# SAM_E54_Xplained_Pro_Target_MCU.net
KiCad netlist of a schematic drawn in Altium Designer
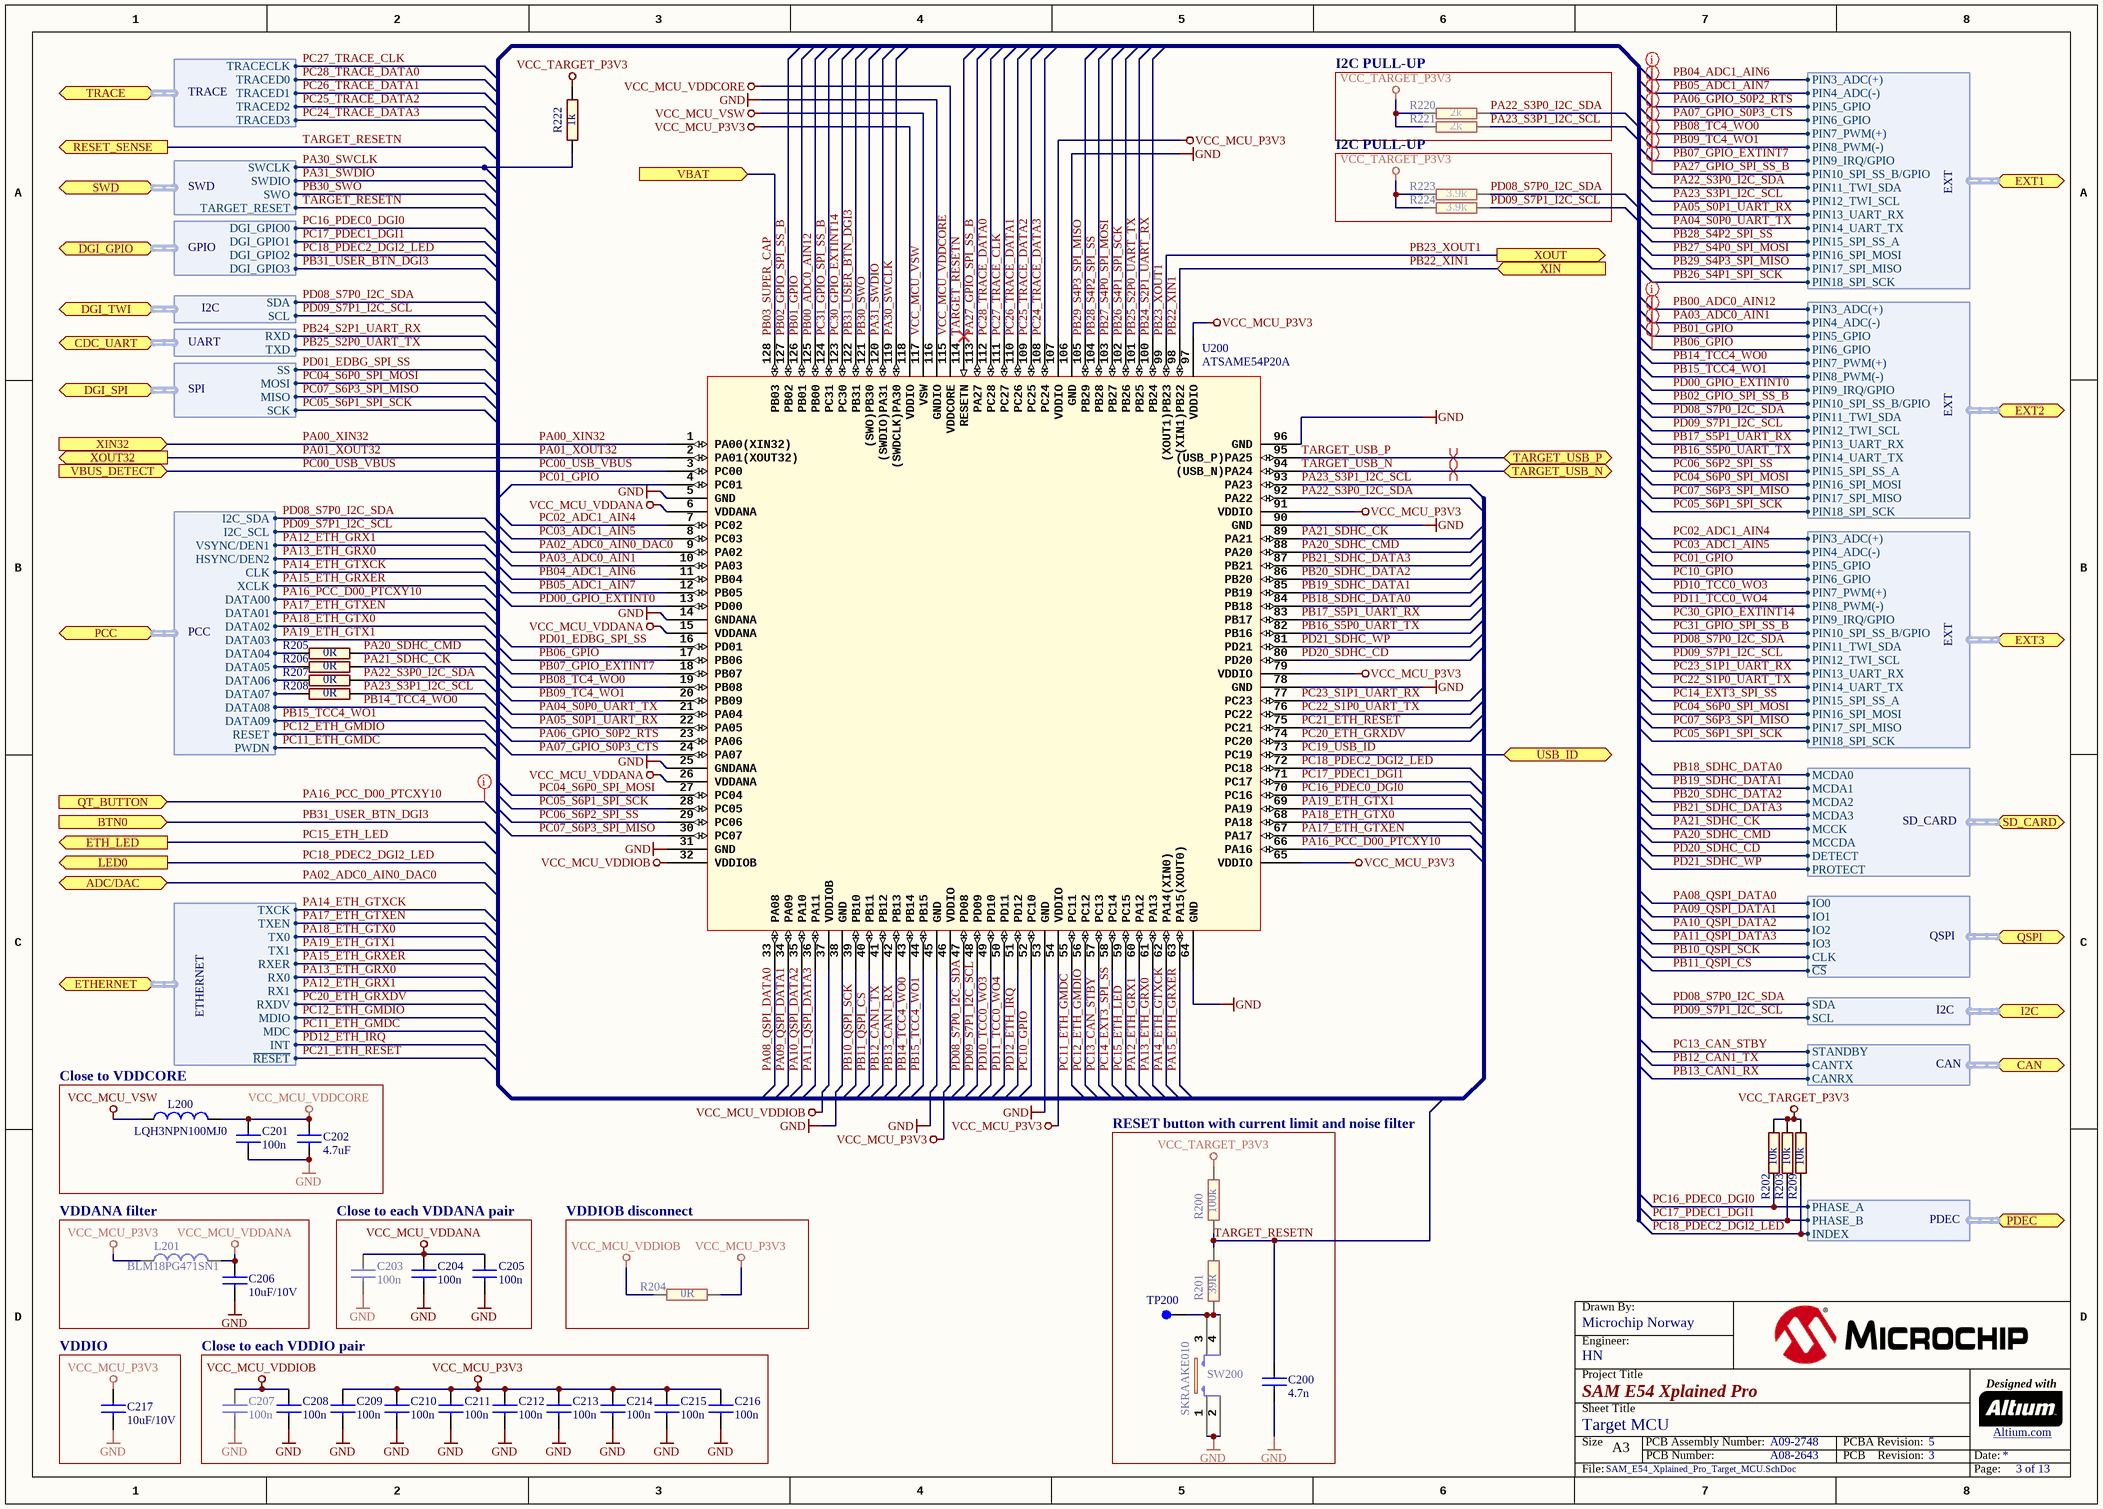
[diagram p0: SAM_E54_Xplained_Pro_Target_MCU.SchDoc]

(export (version "E")
  (design (tool "Eeschema 10.0.6"))
  (components
    (comp (ref "C200")
      (value "4.7n")
      (footprint "AP1-00053")
      (description "Ceramic capacitor, SMD 0402, X7R, 25V, +/-10% (de35287)")
      (fields (field (name "TOLERANCE") "25V, +/-10%") (field (name "MANUFACTURER") "PHYCOMP"))
      (libsource (lib "AltiumDbLib") (part "CAP-NONPOL"))
    )
    (comp (ref "C201")
      (value "100n")
      (footprint "AP1-00053")
      (description "Ceramic capacitor, SMD 0402, X7R, 16V, +/-10%")
      (fields (field (name "TOLERANCE") "16V, +/-10%") (field (name "MANUFACTURER") "Kemet"))
      (libsource (lib "AltiumDbLib") (part "CAP-NONPOL"))
    )
    (comp (ref "C202")
      (value "4.7uF")
      (footprint "AP1-00117")
      (description "Ceramic capacitor, SMD 0603, X5R, 10V, 10% (de31036)")
      (fields (field (name "TOLERANCE") "10%") (field (name "MANUFACTURER") "WALSIN Technology Corporation"))
      (libsource (lib "AltiumDbLib") (part "CAP-NONPOL"))
    )
    (comp (ref "C203")
      (value "100n")
      (footprint "AP1-00053")
      (description "Ceramic capacitor, SMD 0402, X7R, 16V, +/-10%")
      (fields (field (name "TOLERANCE") "16V, +/-10%") (field (name "MANUFACTURER") "Kemet"))
      (libsource (lib "AltiumDbLib") (part "CAP-NONPOL"))
    )
    (comp (ref "C204")
      (value "100n")
      (footprint "AP1-00053")
      (description "Ceramic capacitor, SMD 0402, X7R, 16V, +/-10%")
      (fields (field (name "TOLERANCE") "16V, +/-10%") (field (name "MANUFACTURER") "Kemet"))
      (libsource (lib "AltiumDbLib") (part "CAP-NONPOL"))
    )
    (comp (ref "C205")
      (value "100n")
      (footprint "AP1-00053")
      (description "Ceramic capacitor, SMD 0402, X7R, 16V, +/-10%")
      (fields (field (name "TOLERANCE") "16V, +/-10%") (field (name "MANUFACTURER") "Kemet"))
      (libsource (lib "AltiumDbLib") (part "CAP-NONPOL"))
    )
    (comp (ref "C206")
      (value "10uF/10V")
      (footprint "AP1-00117")
      (description "Ceramic capacitor, SMD 0603, X5R, 10V, 10UF Â± 20%")
      (fields (field (name "MANUFACTURER") "AVX") (field (name "MPN") "0603ZD106MAT2A"))
      (libsource (lib "AltiumDbLib") (part "CAP-NONPOL"))
    )
    (comp (ref "C207")
      (value "100n")
      (footprint "AP1-00053")
      (description "Ceramic capacitor, SMD 0402, X7R, 16V, +/-10%")
      (fields (field (name "TOLERANCE") "16V, +/-10%") (field (name "MANUFACTURER") "Kemet"))
      (libsource (lib "AltiumDbLib") (part "CAP-NONPOL"))
    )
    (comp (ref "C208")
      (value "100n")
      (footprint "AP1-00053")
      (description "Ceramic capacitor, SMD 0402, X7R, 16V, +/-10%")
      (fields (field (name "TOLERANCE") "16V, +/-10%") (field (name "MANUFACTURER") "Kemet"))
      (libsource (lib "AltiumDbLib") (part "CAP-NONPOL"))
    )
    (comp (ref "C209")
      (value "100n")
      (footprint "AP1-00053")
      (description "Ceramic capacitor, SMD 0402, X7R, 16V, +/-10%")
      (fields (field (name "TOLERANCE") "16V, +/-10%") (field (name "MANUFACTURER") "Kemet"))
      (libsource (lib "AltiumDbLib") (part "CAP-NONPOL"))
    )
    (comp (ref "C210")
      (value "100n")
      (footprint "AP1-00053")
      (description "Ceramic capacitor, SMD 0402, X7R, 16V, +/-10%")
      (fields (field (name "TOLERANCE") "16V, +/-10%") (field (name "MANUFACTURER") "Kemet"))
      (libsource (lib "AltiumDbLib") (part "CAP-NONPOL"))
    )
    (comp (ref "C211")
      (value "100n")
      (footprint "AP1-00053")
      (description "Ceramic capacitor, SMD 0402, X7R, 16V, +/-10%")
      (fields (field (name "TOLERANCE") "16V, +/-10%") (field (name "MANUFACTURER") "Kemet"))
      (libsource (lib "AltiumDbLib") (part "CAP-NONPOL"))
    )
    (comp (ref "C212")
      (value "100n")
      (footprint "AP1-00053")
      (description "Ceramic capacitor, SMD 0402, X7R, 16V, +/-10%")
      (fields (field (name "TOLERANCE") "16V, +/-10%") (field (name "MANUFACTURER") "Kemet"))
      (libsource (lib "AltiumDbLib") (part "CAP-NONPOL"))
    )
    (comp (ref "C213")
      (value "100n")
      (footprint "AP1-00053")
      (description "Ceramic capacitor, SMD 0402, X7R, 16V, +/-10%")
      (fields (field (name "TOLERANCE") "16V, +/-10%") (field (name "MANUFACTURER") "Kemet"))
      (libsource (lib "AltiumDbLib") (part "CAP-NONPOL"))
    )
    (comp (ref "C214")
      (value "100n")
      (footprint "AP1-00053")
      (description "Ceramic capacitor, SMD 0402, X7R, 16V, +/-10%")
      (fields (field (name "TOLERANCE") "16V, +/-10%") (field (name "MANUFACTURER") "Kemet"))
      (libsource (lib "AltiumDbLib") (part "CAP-NONPOL"))
    )
    (comp (ref "C215")
      (value "100n")
      (footprint "AP1-00053")
      (description "Ceramic capacitor, SMD 0402, X7R, 16V, +/-10%")
      (fields (field (name "TOLERANCE") "16V, +/-10%") (field (name "MANUFACTURER") "Kemet"))
      (libsource (lib "AltiumDbLib") (part "CAP-NONPOL"))
    )
    (comp (ref "C216")
      (value "100n")
      (footprint "AP1-00053")
      (description "Ceramic capacitor, SMD 0402, X7R, 16V, +/-10%")
      (fields (field (name "TOLERANCE") "16V, +/-10%") (field (name "MANUFACTURER") "Kemet"))
      (libsource (lib "AltiumDbLib") (part "CAP-NONPOL"))
    )
    (comp (ref "C217")
      (value "10uF/10V")
      (footprint "AP1-00117")
      (description "Ceramic capacitor, SMD 0603, X5R, 10V, 10UF Â± 20%")
      (fields (field (name "MANUFACTURER") "AVX") (field (name "MPN") "0603ZD106MAT2A"))
      (libsource (lib "AltiumDbLib") (part "CAP-NONPOL"))
    )
    (comp (ref "L200")
      (value "LQH3NPN100MJ0")
      (footprint "AP3-00115")
      (description "10uH power inductor, Isat = 560mA , Itemp = 710mA, Rdc = 0.360ohm")
      (fields (field (name "TOLERANCE") "Â±20%") (field (name "MANUFACTURER") "Murata"))
      (libsource (lib "AltiumDbLib") (part "INDUCTOR"))
    )
    (comp (ref "L201")
      (value "BLM18PG471SN1")
      (footprint "AP3-00005")
      (description "SMD RF inductor 0603. Z=470Ohm (@100MHz), Max R(dc)=0.65Ohm, Max current=1A")
      (fields (field (name "MANUFACTURER") "Murata"))
      (libsource (lib "AltiumDbLib") (part "INDUCTOR"))
    )
    (comp (ref "R200")
      (value "100k")
      (footprint "AP2-00011")
      (description "Thick film resistor, SMD 0402, 1/16W, 1%")
      (fields (field (name "TOLERANCE") "1 %") (field (name "MANUFACTURER") "ASJ"))
      (libsource (lib "AltiumDbLib") (part "R2"))
    )
    (comp (ref "R201")
      (value "39R")
      (footprint "AP2-00011")
      (description "Thick film resistor, SMD 0402, 1/16W, 1%")
      (fields (field (name "TOLERANCE") "1 %") (field (name "MANUFACTURER") "ASJ"))
      (libsource (lib "") (part "R2_3"))
    )
    (comp (ref "R202")
      (value "10k")
      (footprint "AP2-00011")
      (description "Thick film resistor, SMD 0402, 1/16W, 1%")
      (fields (field (name "TOLERANCE") "1 %") (field (name "MANUFACTURER") "vishay"))
      (libsource (lib "AltiumDbLib") (part "R2"))
    )
    (comp (ref "R203")
      (value "10k")
      (footprint "AP2-00011")
      (description "Thick film resistor, SMD 0402, 1/16W, 1%")
      (fields (field (name "TOLERANCE") "1 %") (field (name "MANUFACTURER") "vishay"))
      (libsource (lib "") (part "R2_2"))
    )
    (comp (ref "R204")
      (value "0R")
      (footprint "AP2-00000")
      (description "RES 0.0 OHM 1/16W 0402 SMD")
      (fields (field (name "TOLERANCE") "1 %") (field (name "MANUFACTURER") "(n/a)"))
      (libsource (lib "") (part "R2_1"))
    )
    (comp (ref "R205")
      (value "0R")
      (footprint "AP2-00000")
      (description "RES 0.0 OHM 1/16W 0402 SMD")
      (fields (field (name "TOLERANCE") "1 %") (field (name "MANUFACTURER") "(n/a)"))
      (libsource (lib "") (part "R2_1"))
    )
    (comp (ref "R206")
      (value "0R")
      (footprint "AP2-00000")
      (description "RES 0.0 OHM 1/16W 0402 SMD")
      (fields (field (name "TOLERANCE") "1 %") (field (name "MANUFACTURER") "(n/a)"))
      (libsource (lib "") (part "R2_1"))
    )
    (comp (ref "R207")
      (value "0R")
      (footprint "AP2-00000")
      (description "RES 0.0 OHM 1/16W 0402 SMD")
      (fields (field (name "TOLERANCE") "1 %") (field (name "MANUFACTURER") "(n/a)"))
      (libsource (lib "") (part "R2_1"))
    )
    (comp (ref "R208")
      (value "0R")
      (footprint "AP2-00000")
      (description "RES 0.0 OHM 1/16W 0402 SMD")
      (fields (field (name "TOLERANCE") "1 %") (field (name "MANUFACTURER") "(n/a)"))
      (libsource (lib "") (part "R2_1"))
    )
    (comp (ref "R209")
      (value "10k")
      (footprint "AP2-00011")
      (description "Thick film resistor, SMD 0402, 1/16W, 1%")
      (fields (field (name "TOLERANCE") "1 %") (field (name "MANUFACTURER") "vishay"))
      (libsource (lib "") (part "R2_2"))
    )
    (comp (ref "R220")
      (value "2k")
      (footprint "AP2-00011")
      (description "Thick film resistor, SMD 0402, 1/16W, 1%")
      (fields (field (name "TOLERANCE") "1 %"))
      (libsource (lib "") (part "R2_1"))
    )
    (comp (ref "R221")
      (value "2k")
      (footprint "AP2-00011")
      (description "Thick film resistor, SMD 0402, 1/16W, 1%")
      (fields (field (name "TOLERANCE") "1 %"))
      (libsource (lib "") (part "R2_1"))
    )
    (comp (ref "R222")
      (value "1k")
      (footprint "AP2-00011")
      (description "Thick film resistor, SMD 0402, 1/16W, 1%")
      (fields (field (name "TOLERANCE") "1 %") (field (name "MANUFACTURER") "ASJ"))
      (libsource (lib "AltiumDbLib") (part "R2"))
    )
    (comp (ref "R223")
      (value "3.9k")
      (footprint "AP2-00011")
      (description "Thick film resistor, SMD 0402, 1/16W, 1%")
      (fields (field (name "TOLERANCE") "1 %"))
      (libsource (lib "") (part "R2_1"))
    )
    (comp (ref "R224")
      (value "3.9k")
      (footprint "AP2-00011")
      (description "Thick film resistor, SMD 0402, 1/16W, 1%")
      (fields (field (name "TOLERANCE") "1 %"))
      (libsource (lib "") (part "R2_1"))
    )
    (comp (ref "SW200")
      (value "SKRAAKE010")
      (footprint "AP8-00137")
      (description "6.2x6.2 mm SMD tact switch, same as A08-0091 but less force is needed")
      (fields (field (name "MANUFACTURER") "ALPS"))
      (libsource (lib "AltiumDbLib") (part "PUSHBUTTON1"))
    )
    (comp (ref "TP200")
      (value "~")
      (footprint "AP8-00010")
      (description "Single SMD testpad")
      (libsource (lib "AltiumDbLib") (part "TESTPOINT"))
    )
    (comp (ref "U200")
      (value "ATSAME54P20A")
      (footprint "AP6-00477")
      (description "Atmel 32-bit RISC MCU")
      (fields (field (name "MANUFACTURER") "ATMEL") (field (name "MPN") "ATSAME54P20A-AUT"))
      (libsource (lib "AltiumDbLib") (part "SAME54_TQFP128"))
    )
  )
  (nets
    (net (code "15") (name "/DATA04") (class "Default")
      (node (ref "R205") (pin "2") (pinfunction "2_2") (pintype "passive"))
    )
    (net (code "16") (name "/DATA05") (class "Default")
      (node (ref "R206") (pin "2") (pinfunction "2_2") (pintype "passive"))
    )
    (net (code "17") (name "/DATA06") (class "Default")
      (node (ref "R207") (pin "2") (pinfunction "2_2") (pintype "passive"))
    )
    (net (code "18") (name "/DATA07") (class "Default")
      (node (ref "R208") (pin "2") (pinfunction "2_2") (pintype "passive"))
    )
    (net (code "19") (name "/PA00_XIN32") (class "Default")
      (node (ref "U200") (pin "1") (pinfunction "PA00(XIN32)_1") (pintype "bidirectional"))
    )
    (net (code "20") (name "/PA01_XOUT32") (class "Default")
      (node (ref "U200") (pin "2") (pinfunction "PA01(XOUT32)_2") (pintype "bidirectional"))
    )
    (net (code "21") (name "/PA02_ADC0_AIN0_DAC0") (class "Default")
      (node (ref "U200") (pin "9") (pinfunction "PA02_9") (pintype "bidirectional"))
    )
    (net (code "22") (name "/PA03_ADC0_AIN1") (class "Default")
      (node (ref "U200") (pin "10") (pinfunction "PA03_10") (pintype "bidirectional"))
    )
    (net (code "23") (name "/PA04_S0P0_UART_TX") (class "Default")
      (node (ref "U200") (pin "21") (pinfunction "PA04_21") (pintype "bidirectional"))
    )
    (net (code "24") (name "/PA05_S0P1_UART_RX") (class "Default")
      (node (ref "U200") (pin "22") (pinfunction "PA05_22") (pintype "bidirectional"))
    )
    (net (code "25") (name "/PA06_GPIO_S0P2_RTS") (class "Default")
      (node (ref "U200") (pin "23") (pinfunction "PA06_23") (pintype "bidirectional"))
    )
    (net (code "26") (name "/PA07_GPIO_S0P3_CTS") (class "Default")
      (node (ref "U200") (pin "24") (pinfunction "PA07_24") (pintype "bidirectional"))
    )
    (net (code "27") (name "/PA08_QSPI_DATA0") (class "Default")
      (node (ref "U200") (pin "33") (pinfunction "PA08_33") (pintype "bidirectional"))
    )
    (net (code "28") (name "/PA09_QSPI_DATA1") (class "Default")
      (node (ref "U200") (pin "34") (pinfunction "PA09_34") (pintype "bidirectional"))
    )
    (net (code "29") (name "/PA10_QSPI_DATA2") (class "Default")
      (node (ref "U200") (pin "35") (pinfunction "PA10_35") (pintype "bidirectional"))
    )
    (net (code "30") (name "/PA11_QSPI_DATA3") (class "Default")
      (node (ref "U200") (pin "36") (pinfunction "PA11_36") (pintype "bidirectional"))
    )
    (net (code "31") (name "/PA12_ETH_GRX1") (class "Default")
      (node (ref "U200") (pin "60") (pinfunction "PA12_60") (pintype "bidirectional"))
    )
    (net (code "32") (name "/PA13_ETH_GRX0") (class "Default")
      (node (ref "U200") (pin "61") (pinfunction "PA13_61") (pintype "bidirectional"))
    )
    (net (code "33") (name "/PA14_ETH_GTXCK") (class "Default")
      (node (ref "U200") (pin "62") (pinfunction "PA14(XIN0)_62") (pintype "bidirectional"))
    )
    (net (code "34") (name "/PA15_ETH_GRXER") (class "Default")
      (node (ref "U200") (pin "63") (pinfunction "PA15(XOUT0)_63") (pintype "bidirectional"))
    )
    (net (code "35") (name "/PA16_PCC_D00_PTCXY10") (class "Default")
      (node (ref "U200") (pin "66") (pinfunction "PA16_66") (pintype "bidirectional"))
    )
    (net (code "36") (name "/PA17_ETH_GTXEN") (class "Default")
      (node (ref "U200") (pin "67") (pinfunction "PA17_67") (pintype "bidirectional"))
    )
    (net (code "37") (name "/PA18_ETH_GTX0") (class "Default")
      (node (ref "U200") (pin "68") (pinfunction "PA18_68") (pintype "bidirectional"))
    )
    (net (code "38") (name "/PA19_ETH_GTX1") (class "Default")
      (node (ref "U200") (pin "69") (pinfunction "PA19_69") (pintype "bidirectional"))
    )
    (net (code "39") (name "/PA20_SDHC_CMD") (class "Default")
      (node (ref "R205") (pin "1") (pinfunction "1_1") (pintype "passive"))
      (node (ref "U200") (pin "88") (pinfunction "PA20_88") (pintype "bidirectional"))
    )
    (net (code "40") (name "/PA21_SDHC_CK") (class "Default")
      (node (ref "R206") (pin "1") (pinfunction "1_1") (pintype "passive"))
      (node (ref "U200") (pin "89") (pinfunction "PA21_89") (pintype "bidirectional"))
    )
    (net (code "41") (name "/PA22_S3P0_I2C_SDA") (class "Default")
      (node (ref "R207") (pin "1") (pinfunction "1_1") (pintype "passive"))
      (node (ref "R220") (pin "1") (pinfunction "1_1") (pintype "passive"))
      (node (ref "U200") (pin "92") (pinfunction "PA22_92") (pintype "bidirectional"))
    )
    (net (code "42") (name "/PA23_S3P1_I2C_SCL") (class "Default")
      (node (ref "R208") (pin "1") (pinfunction "1_1") (pintype "passive"))
      (node (ref "R221") (pin "1") (pinfunction "1_1") (pintype "passive"))
      (node (ref "U200") (pin "93") (pinfunction "PA23_93") (pintype "bidirectional"))
    )
    (net (code "43") (name "/PA27_GPIO_SPI_SS_B") (class "Default")
      (node (ref "U200") (pin "113") (pinfunction "PA27_113") (pintype "bidirectional"))
    )
    (net (code "44") (name "/PA30_SWCLK") (class "Default")
      (node (ref "R222") (pin "1") (pinfunction "1_1") (pintype "passive"))
      (node (ref "U200") (pin "119") (pinfunction "(SWDCLK)PA30_119") (pintype "bidirectional"))
    )
    (net (code "45") (name "/PA31_SWDIO") (class "Default")
      (node (ref "U200") (pin "120") (pinfunction "(SWDIO)PA31_120") (pintype "bidirectional"))
    )
    (net (code "46") (name "/PB00_ADC0_AIN12") (class "Default")
      (node (ref "U200") (pin "125") (pinfunction "PB00_125") (pintype "bidirectional"))
    )
    (net (code "47") (name "/PB01_GPIO") (class "Default")
      (node (ref "U200") (pin "126") (pinfunction "PB01_126") (pintype "bidirectional"))
    )
    (net (code "48") (name "/PB02_GPIO_SPI_SS_B") (class "Default")
      (node (ref "U200") (pin "127") (pinfunction "PB02_127") (pintype "bidirectional"))
    )
    (net (code "49") (name "/PB03_SUPER_CAP") (class "Default")
      (node (ref "U200") (pin "128") (pinfunction "PB03_128") (pintype "bidirectional"))
    )
    (net (code "50") (name "/PB04_ADC1_AIN6") (class "Default")
      (node (ref "U200") (pin "11") (pinfunction "PB04_11") (pintype "bidirectional"))
    )
    (net (code "51") (name "/PB05_ADC1_AIN7") (class "Default")
      (node (ref "U200") (pin "12") (pinfunction "PB05_12") (pintype "bidirectional"))
    )
    (net (code "52") (name "/PB06_GPIO") (class "Default")
      (node (ref "U200") (pin "17") (pinfunction "PB06_17") (pintype "bidirectional"))
    )
    (net (code "53") (name "/PB07_GPIO_EXTINT7") (class "Default")
      (node (ref "U200") (pin "18") (pinfunction "PB07_18") (pintype "bidirectional"))
    )
    (net (code "54") (name "/PB08_TC4_WO0") (class "Default")
      (node (ref "U200") (pin "19") (pinfunction "PB08_19") (pintype "bidirectional"))
    )
    (net (code "55") (name "/PB09_TC4_WO1") (class "Default")
      (node (ref "U200") (pin "20") (pinfunction "PB09_20") (pintype "bidirectional"))
    )
    (net (code "56") (name "/PB10_QSPI_SCK") (class "Default")
      (node (ref "U200") (pin "39") (pinfunction "PB10_39") (pintype "bidirectional"))
    )
    (net (code "57") (name "/PB11_QSPI_CS") (class "Default")
      (node (ref "U200") (pin "40") (pinfunction "PB11_40") (pintype "bidirectional"))
    )
    (net (code "58") (name "/PB12_CAN1_TX") (class "Default")
      (node (ref "U200") (pin "41") (pinfunction "PB12_41") (pintype "bidirectional"))
    )
    (net (code "59") (name "/PB13_CAN1_RX") (class "Default")
      (node (ref "U200") (pin "42") (pinfunction "PB13_42") (pintype "bidirectional"))
    )
    (net (code "60") (name "/PB14_TCC4_WO0") (class "Default")
      (node (ref "U200") (pin "43") (pinfunction "PB14_43") (pintype "bidirectional"))
    )
    (net (code "61") (name "/PB15_TCC4_WO1") (class "Default")
      (node (ref "U200") (pin "44") (pinfunction "PB15_44") (pintype "bidirectional"))
    )
    (net (code "62") (name "/PB16_S5P0_UART_TX") (class "Default")
      (node (ref "U200") (pin "82") (pinfunction "PB16_82") (pintype "bidirectional"))
    )
    (net (code "63") (name "/PB17_S5P1_UART_RX") (class "Default")
      (node (ref "U200") (pin "83") (pinfunction "PB17_83") (pintype "bidirectional"))
    )
    (net (code "64") (name "/PB18_SDHC_DATA0") (class "Default")
      (node (ref "U200") (pin "84") (pinfunction "PB18_84") (pintype "bidirectional"))
    )
    (net (code "65") (name "/PB19_SDHC_DATA1") (class "Default")
      (node (ref "U200") (pin "85") (pinfunction "PB19_85") (pintype "bidirectional"))
    )
    (net (code "66") (name "/PB20_SDHC_DATA2") (class "Default")
      (node (ref "U200") (pin "86") (pinfunction "PB20_86") (pintype "bidirectional"))
    )
    (net (code "67") (name "/PB21_SDHC_DATA3") (class "Default")
      (node (ref "U200") (pin "87") (pinfunction "PB21_87") (pintype "bidirectional"))
    )
    (net (code "68") (name "/PB22_XIN1") (class "Default")
      (node (ref "U200") (pin "98") (pinfunction "(XIN1)PB22_98") (pintype "bidirectional"))
    )
    (net (code "69") (name "/PB23_XOUT1") (class "Default")
      (node (ref "U200") (pin "99") (pinfunction "(XOUT1)PB23_99") (pintype "bidirectional"))
    )
    (net (code "70") (name "/PB24_S2P1_UART_RX") (class "Default")
      (node (ref "U200") (pin "100") (pinfunction "PB24_100") (pintype "bidirectional"))
    )
    (net (code "71") (name "/PB25_S2P0_UART_TX") (class "Default")
      (node (ref "U200") (pin "101") (pinfunction "PB25_101") (pintype "bidirectional"))
    )
    (net (code "72") (name "/PB26_S4P1_SPI_SCK") (class "Default")
      (node (ref "U200") (pin "102") (pinfunction "PB26_102") (pintype "bidirectional"))
    )
    (net (code "73") (name "/PB27_S4P0_SPI_MOSI") (class "Default")
      (node (ref "U200") (pin "103") (pinfunction "PB27_103") (pintype "bidirectional"))
    )
    (net (code "74") (name "/PB28_S4P2_SPI_SS") (class "Default")
      (node (ref "U200") (pin "104") (pinfunction "PB28_104") (pintype "bidirectional"))
    )
    (net (code "75") (name "/PB29_S4P3_SPI_MISO") (class "Default")
      (node (ref "U200") (pin "105") (pinfunction "PB29_105") (pintype "bidirectional"))
    )
    (net (code "76") (name "/PB30_SWO") (class "Default")
      (node (ref "U200") (pin "121") (pinfunction "(SWO)PB30_121") (pintype "bidirectional"))
    )
    (net (code "77") (name "/PB31_USER_BTN_DGI3") (class "Default")
      (node (ref "U200") (pin "122") (pinfunction "PB31_122") (pintype "bidirectional"))
    )
    (net (code "78") (name "/PC00_USB_VBUS") (class "Default")
      (node (ref "U200") (pin "3") (pinfunction "PC00_3") (pintype "bidirectional"))
    )
    (net (code "79") (name "/PC01_GPIO") (class "Default")
      (node (ref "U200") (pin "4") (pinfunction "PC01_4") (pintype "bidirectional"))
    )
    (net (code "80") (name "/PC02_ADC1_AIN4") (class "Default")
      (node (ref "U200") (pin "7") (pinfunction "PC02_7") (pintype "bidirectional"))
    )
    (net (code "81") (name "/PC03_ADC1_AIN5") (class "Default")
      (node (ref "U200") (pin "8") (pinfunction "PC03_8") (pintype "bidirectional"))
    )
    (net (code "82") (name "/PC04_S6P0_SPI_MOSI") (class "Default")
      (node (ref "U200") (pin "27") (pinfunction "PC04_27") (pintype "bidirectional"))
    )
    (net (code "83") (name "/PC05_S6P1_SPI_SCK") (class "Default")
      (node (ref "U200") (pin "28") (pinfunction "PC05_28") (pintype "bidirectional"))
    )
    (net (code "84") (name "/PC06_S6P2_SPI_SS") (class "Default")
      (node (ref "U200") (pin "29") (pinfunction "PC06_29") (pintype "bidirectional"))
    )
    (net (code "85") (name "/PC07_S6P3_SPI_MISO") (class "Default")
      (node (ref "U200") (pin "30") (pinfunction "PC07_30") (pintype "bidirectional"))
    )
    (net (code "86") (name "/PC10_GPIO") (class "Default")
      (node (ref "U200") (pin "52") (pinfunction "PC10_52") (pintype "bidirectional"))
    )
    (net (code "87") (name "/PC11_ETH_GMDC") (class "Default")
      (node (ref "U200") (pin "55") (pinfunction "PC11_55") (pintype "bidirectional"))
    )
    (net (code "88") (name "/PC12_ETH_GMDIO") (class "Default")
      (node (ref "U200") (pin "56") (pinfunction "PC12_56") (pintype "bidirectional"))
    )
    (net (code "89") (name "/PC13_CAN_STBY") (class "Default")
      (node (ref "U200") (pin "57") (pinfunction "PC13_57") (pintype "bidirectional"))
    )
    (net (code "90") (name "/PC14_EXT3_SPI_SS") (class "Default")
      (node (ref "U200") (pin "58") (pinfunction "PC14_58") (pintype "bidirectional"))
    )
    (net (code "91") (name "/PC15_ETH_LED") (class "Default")
      (node (ref "U200") (pin "59") (pinfunction "PC15_59") (pintype "bidirectional"))
    )
    (net (code "92") (name "/PC16_PDEC0_DGI0") (class "Default")
      (node (ref "R202") (pin "1") (pinfunction "1_1") (pintype "passive"))
      (node (ref "U200") (pin "70") (pinfunction "PC16_70") (pintype "bidirectional"))
    )
    (net (code "93") (name "/PC17_PDEC1_DGI1") (class "Default")
      (node (ref "R203") (pin "2") (pinfunction "2_2") (pintype "passive"))
      (node (ref "U200") (pin "71") (pinfunction "PC17_71") (pintype "bidirectional"))
    )
    (net (code "94") (name "/PC18_PDEC2_DGI2_LED") (class "Default")
      (node (ref "R209") (pin "2") (pinfunction "2_2") (pintype "passive"))
      (node (ref "U200") (pin "72") (pinfunction "PC18_72") (pintype "bidirectional"))
    )
    (net (code "95") (name "/PC19_USB_ID") (class "Default")
      (node (ref "U200") (pin "73") (pinfunction "PC19_73") (pintype "bidirectional"))
    )
    (net (code "96") (name "/PC20_ETH_GRXDV") (class "Default")
      (node (ref "U200") (pin "74") (pinfunction "PC20_74") (pintype "bidirectional"))
    )
    (net (code "97") (name "/PC21_ETH_RESET") (class "Default")
      (node (ref "U200") (pin "75") (pinfunction "PC21_75") (pintype "bidirectional"))
    )
    (net (code "98") (name "/PC22_S1P0_UART_TX") (class "Default")
      (node (ref "U200") (pin "76") (pinfunction "PC22_76") (pintype "bidirectional"))
    )
    (net (code "99") (name "/PC23_S1P1_UART_RX") (class "Default")
      (node (ref "U200") (pin "77") (pinfunction "PC23_77") (pintype "bidirectional"))
    )
    (net (code "100") (name "/PC24_TRACE_DATA3") (class "Default")
      (node (ref "U200") (pin "108") (pinfunction "PC24_108") (pintype "bidirectional"))
    )
    (net (code "101") (name "/PC25_TRACE_DATA2") (class "Default")
      (node (ref "U200") (pin "109") (pinfunction "PC25_109") (pintype "bidirectional"))
    )
    (net (code "102") (name "/PC26_TRACE_DATA1") (class "Default")
      (node (ref "U200") (pin "110") (pinfunction "PC26_110") (pintype "bidirectional"))
    )
    (net (code "103") (name "/PC27_TRACE_CLK") (class "Default")
      (node (ref "U200") (pin "111") (pinfunction "PC27_111") (pintype "bidirectional"))
    )
    (net (code "104") (name "/PC28_TRACE_DATA0") (class "Default")
      (node (ref "U200") (pin "112") (pinfunction "PC28_112") (pintype "bidirectional"))
    )
    (net (code "105") (name "/PC30_GPIO_EXTINT14") (class "Default")
      (node (ref "U200") (pin "123") (pinfunction "PC30_123") (pintype "bidirectional"))
    )
    (net (code "106") (name "/PC31_GPIO_SPI_SS_B") (class "Default")
      (node (ref "U200") (pin "124") (pinfunction "PC31_124") (pintype "bidirectional"))
    )
    (net (code "107") (name "/PD00_GPIO_EXTINT0") (class "Default")
      (node (ref "U200") (pin "13") (pinfunction "PD00_13") (pintype "bidirectional"))
    )
    (net (code "108") (name "/PD01_EDBG_SPI_SS") (class "Default")
      (node (ref "U200") (pin "16") (pinfunction "PD01_16") (pintype "bidirectional"))
    )
    (net (code "109") (name "/PD08_S7P0_I2C_SDA") (class "Default")
      (node (ref "R223") (pin "1") (pinfunction "1_1") (pintype "passive"))
      (node (ref "U200") (pin "47") (pinfunction "PD08_47") (pintype "bidirectional"))
    )
    (net (code "110") (name "/PD09_S7P1_I2C_SCL") (class "Default")
      (node (ref "R224") (pin "1") (pinfunction "1_1") (pintype "passive"))
      (node (ref "U200") (pin "48") (pinfunction "PD09_48") (pintype "bidirectional"))
    )
    (net (code "111") (name "/PD10_TCC0_WO3") (class "Default")
      (node (ref "U200") (pin "49") (pinfunction "PD10_49") (pintype "bidirectional"))
    )
    (net (code "112") (name "/PD11_TCC0_WO4") (class "Default")
      (node (ref "U200") (pin "50") (pinfunction "PD11_50") (pintype "bidirectional"))
    )
    (net (code "113") (name "/PD12_ETH_IRQ") (class "Default")
      (node (ref "U200") (pin "51") (pinfunction "PD12_51") (pintype "bidirectional"))
    )
    (net (code "114") (name "/PD20_SDHC_CD") (class "Default")
      (node (ref "U200") (pin "80") (pinfunction "PD20_80") (pintype "bidirectional"))
    )
    (net (code "115") (name "/PD21_SDHC_WP") (class "Default")
      (node (ref "U200") (pin "81") (pinfunction "PD21_81") (pintype "bidirectional"))
    )
    (net (code "116") (name "/TARGET_RESETN") (class "Default")
      (node (ref "C200") (pin "1") (pinfunction "1_1") (pintype "passive"))
      (node (ref "R200") (pin "1") (pinfunction "1_1") (pintype "passive"))
      (node (ref "R201") (pin "2") (pinfunction "2_2") (pintype "passive"))
      (node (ref "U200") (pin "114") (pinfunction "RESETN_114") (pintype "input"))
    )
    (net (code "117") (name "/TARGET_USB_N") (class "Default")
      (node (ref "U200") (pin "94") (pinfunction "(USB_N)PA24_94") (pintype "bidirectional"))
    )
    (net (code "118") (name "/TARGET_USB_P") (class "Default")
      (node (ref "U200") (pin "95") (pinfunction "(USB_P)PA25_95") (pintype "bidirectional"))
    )
    (net (code "131") (name "GND") (class "Default")
      (node (ref "C200") (pin "2") (pinfunction "2_2") (pintype "passive"))
      (node (ref "C201") (pin "2") (pinfunction "2_2") (pintype "passive"))
      (node (ref "C202") (pin "2") (pinfunction "2_2") (pintype "passive"))
      (node (ref "C203") (pin "2") (pinfunction "2_2") (pintype "passive"))
      (node (ref "C204") (pin "2") (pinfunction "2_2") (pintype "passive"))
      (node (ref "C205") (pin "2") (pinfunction "2_2") (pintype "passive"))
      (node (ref "C206") (pin "2") (pinfunction "2_2") (pintype "passive"))
      (node (ref "C207") (pin "2") (pinfunction "2_2") (pintype "passive"))
      (node (ref "C208") (pin "2") (pinfunction "2_2") (pintype "passive"))
      (node (ref "C209") (pin "2") (pinfunction "2_2") (pintype "passive"))
      (node (ref "C210") (pin "2") (pinfunction "2_2") (pintype "passive"))
      (node (ref "C211") (pin "2") (pinfunction "2_2") (pintype "passive"))
      (node (ref "C212") (pin "2") (pinfunction "2_2") (pintype "passive"))
      (node (ref "C213") (pin "2") (pinfunction "2_2") (pintype "passive"))
      (node (ref "C214") (pin "2") (pinfunction "2_2") (pintype "passive"))
      (node (ref "C215") (pin "2") (pinfunction "2_2") (pintype "passive"))
      (node (ref "C216") (pin "2") (pinfunction "2_2") (pintype "passive"))
      (node (ref "C217") (pin "2") (pinfunction "2_2") (pintype "passive"))
      (node (ref "SW200") (pin "1") (pinfunction "1_1") (pintype "passive"))
      (node (ref "SW200") (pin "2") (pinfunction "2_2") (pintype "passive"))
      (node (ref "U200") (pin "106") (pinfunction "GND_106") (pintype "power_in"))
      (node (ref "U200") (pin "116") (pinfunction "GNDIO_116") (pintype "power_in"))
      (node (ref "U200") (pin "14") (pinfunction "GNDANA_14") (pintype "power_in"))
      (node (ref "U200") (pin "25") (pinfunction "GNDANA_25") (pintype "power_in"))
      (node (ref "U200") (pin "31") (pinfunction "GND_31") (pintype "power_in"))
      (node (ref "U200") (pin "38") (pinfunction "GND_38") (pintype "power_in"))
      (node (ref "U200") (pin "45") (pinfunction "GND_45") (pintype "power_in"))
      (node (ref "U200") (pin "5") (pinfunction "GND_5") (pintype "power_in"))
      (node (ref "U200") (pin "53") (pinfunction "GND_53") (pintype "power_in"))
      (node (ref "U200") (pin "64") (pinfunction "GND_64") (pintype "power_in"))
      (node (ref "U200") (pin "78") (pinfunction "GND_78") (pintype "power_in"))
      (node (ref "U200") (pin "90") (pinfunction "GND_90") (pintype "power_in"))
      (node (ref "U200") (pin "96") (pinfunction "GND_96") (pintype "power_in"))
    )
    (net (code "132") (name "Net-(R201-Pad1)") (class "Default")
      (node (ref "R201") (pin "1") (pinfunction "1_1") (pintype "passive"))
      (node (ref "SW200") (pin "3") (pinfunction "3_3") (pintype "passive"))
      (node (ref "SW200") (pin "4") (pinfunction "4_4") (pintype "passive"))
      (node (ref "TP200") (pin "1") (pinfunction "1_1") (pintype "passive"))
    )
    (net (code "133") (name "VCC_MCU_P3V3") (class "Default")
      (node (ref "C209") (pin "1") (pinfunction "1_1") (pintype "passive"))
      (node (ref "C210") (pin "1") (pinfunction "1_1") (pintype "passive"))
      (node (ref "C211") (pin "1") (pinfunction "1_1") (pintype "passive"))
      (node (ref "C212") (pin "1") (pinfunction "1_1") (pintype "passive"))
      (node (ref "C213") (pin "1") (pinfunction "1_1") (pintype "passive"))
      (node (ref "C214") (pin "1") (pinfunction "1_1") (pintype "passive"))
      (node (ref "C215") (pin "1") (pinfunction "1_1") (pintype "passive"))
      (node (ref "C216") (pin "1") (pinfunction "1_1") (pintype "passive"))
      (node (ref "C217") (pin "1") (pinfunction "1_1") (pintype "passive"))
      (node (ref "L201") (pin "1") (pinfunction "1_1") (pintype "passive"))
      (node (ref "R204") (pin "1") (pinfunction "1_1") (pintype "passive"))
      (node (ref "U200") (pin "107") (pinfunction "VDDIO_107") (pintype "power_in"))
      (node (ref "U200") (pin "118") (pinfunction "VDDIO_118") (pintype "power_in"))
      (node (ref "U200") (pin "46") (pinfunction "VDDIO_46") (pintype "power_in"))
      (node (ref "U200") (pin "54") (pinfunction "VDDIO_54") (pintype "power_in"))
      (node (ref "U200") (pin "65") (pinfunction "VDDIO_65") (pintype "power_in"))
      (node (ref "U200") (pin "79") (pinfunction "VDDIO_79") (pintype "power_in"))
      (node (ref "U200") (pin "91") (pinfunction "VDDIO_91") (pintype "power_in"))
      (node (ref "U200") (pin "97") (pinfunction "VDDIO_97") (pintype "power_in"))
    )
    (net (code "134") (name "VCC_MCU_VDDANA") (class "Default")
      (node (ref "C203") (pin "1") (pinfunction "1_1") (pintype "passive"))
      (node (ref "C204") (pin "1") (pinfunction "1_1") (pintype "passive"))
      (node (ref "C205") (pin "1") (pinfunction "1_1") (pintype "passive"))
      (node (ref "C206") (pin "1") (pinfunction "1_1") (pintype "passive"))
      (node (ref "L201") (pin "2") (pinfunction "2_2") (pintype "passive"))
      (node (ref "U200") (pin "15") (pinfunction "VDDANA_15") (pintype "power_in"))
      (node (ref "U200") (pin "26") (pinfunction "VDDANA_26") (pintype "power_in"))
      (node (ref "U200") (pin "6") (pinfunction "VDDANA_6") (pintype "power_in"))
    )
    (net (code "135") (name "VCC_MCU_VDDCORE") (class "Default")
      (node (ref "C201") (pin "1") (pinfunction "1_1") (pintype "passive"))
      (node (ref "C202") (pin "1") (pinfunction "1_1") (pintype "passive"))
      (node (ref "L200") (pin "2") (pinfunction "2_2") (pintype "passive"))
      (node (ref "U200") (pin "115") (pinfunction "VDDCORE_115") (pintype "power_in"))
    )
    (net (code "136") (name "VCC_MCU_VDDIOB") (class "Default")
      (node (ref "C207") (pin "1") (pinfunction "1_1") (pintype "passive"))
      (node (ref "C208") (pin "1") (pinfunction "1_1") (pintype "passive"))
      (node (ref "R204") (pin "2") (pinfunction "2_2") (pintype "passive"))
      (node (ref "U200") (pin "32") (pinfunction "VDDIOB_32") (pintype "power_in"))
      (node (ref "U200") (pin "37") (pinfunction "VDDIOB_37") (pintype "power_in"))
    )
    (net (code "137") (name "VCC_MCU_VSW") (class "Default")
      (node (ref "L200") (pin "1") (pinfunction "1_1") (pintype "passive"))
      (node (ref "U200") (pin "117") (pinfunction "VSW_117") (pintype "power_in"))
    )
    (net (code "138") (name "VCC_TARGET_P3V3") (class "Default")
      (node (ref "R200") (pin "2") (pinfunction "2_2") (pintype "passive"))
      (node (ref "R202") (pin "2") (pinfunction "2_2") (pintype "passive"))
      (node (ref "R203") (pin "1") (pinfunction "1_1") (pintype "passive"))
      (node (ref "R209") (pin "1") (pinfunction "1_1") (pintype "passive"))
      (node (ref "R220") (pin "2") (pinfunction "2_2") (pintype "passive"))
      (node (ref "R221") (pin "2") (pinfunction "2_2") (pintype "passive"))
      (node (ref "R222") (pin "2") (pinfunction "2_2") (pintype "passive"))
      (node (ref "R223") (pin "2") (pinfunction "2_2") (pintype "passive"))
      (node (ref "R224") (pin "2") (pinfunction "2_2") (pintype "passive"))
    )
  )
)
